# USB-to-Quad-RS-485-Conv-Module.net
KiCad netlist of a schematic drawn in EAGLE
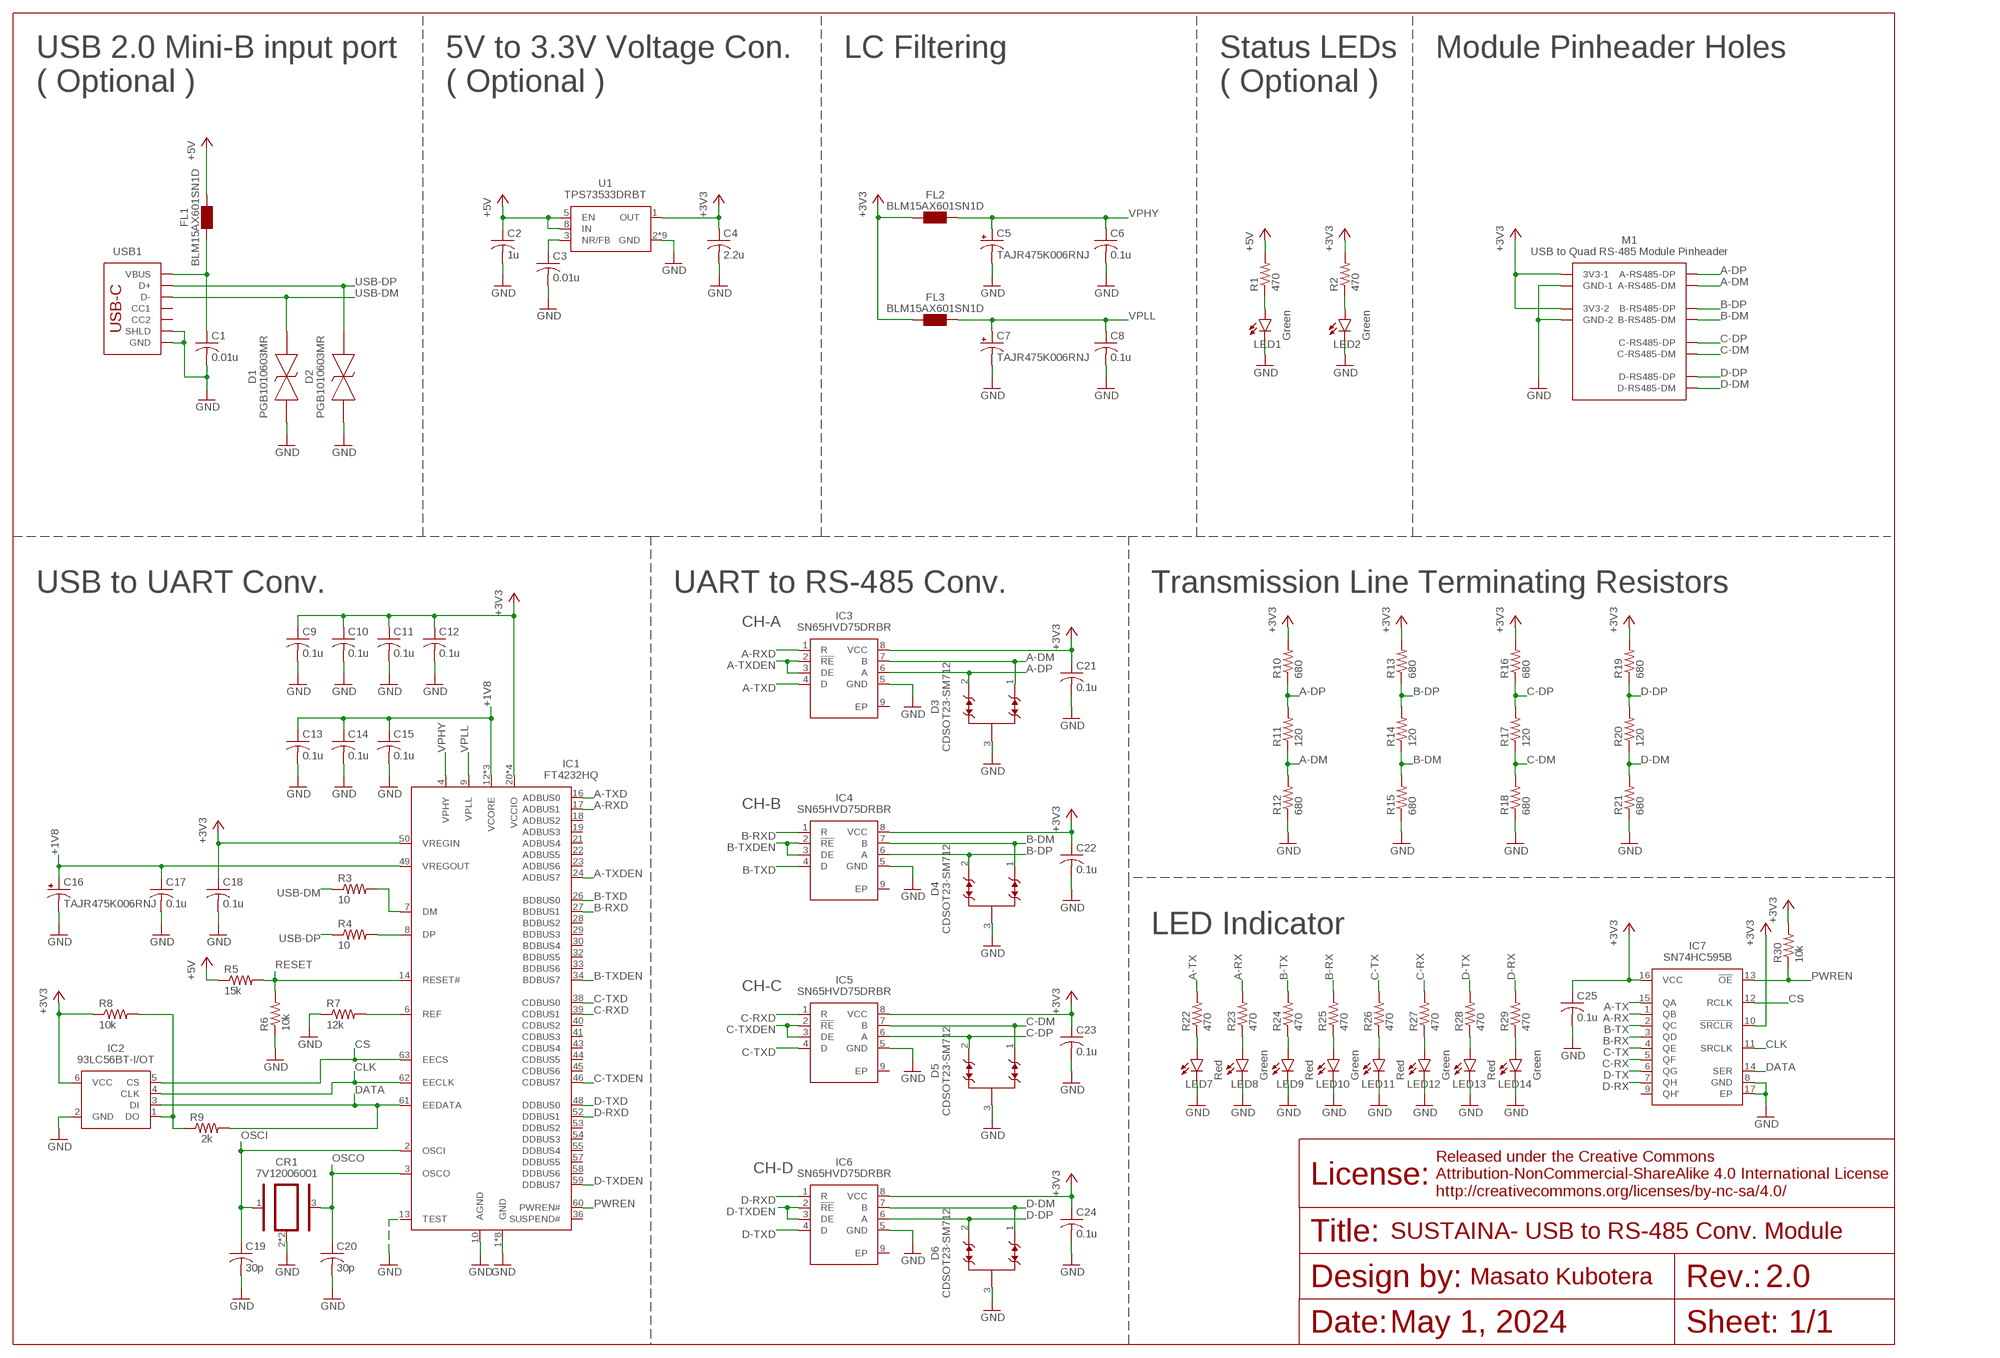
[diagram p0: schematic, sheet 1]

(export (version "E")
  (design (tool "Eeschema 10.0.6"))
  (components
    (comp (ref "C1")
      (value "0.01u")
      (footprint "eagle-import:C0402")
      (libsource (lib "eagle-import") (part "C-USC0402"))
    )
    (comp (ref "C2")
      (value "1u")
      (footprint "eagle-import:C0402")
      (libsource (lib "eagle-import") (part "C-USC0402"))
    )
    (comp (ref "C3")
      (value "0.01u")
      (footprint "eagle-import:C0402")
      (libsource (lib "eagle-import") (part "C-USC0402"))
    )
    (comp (ref "C4")
      (value "2.2u")
      (footprint "eagle-import:C0402")
      (libsource (lib "eagle-import") (part "C-USC0402"))
    )
    (comp (ref "C5")
      (value "4.7u")
      (footprint "eagle-import:0805K")
      (libsource (lib "eagle-import") (part "TAJR475K006RNJ"))
    )
    (comp (ref "C6")
      (value "0.1u")
      (footprint "eagle-import:C0402")
      (libsource (lib "eagle-import") (part "C-USC0402"))
    )
    (comp (ref "C7")
      (value "4.7u")
      (footprint "eagle-import:0805K")
      (libsource (lib "eagle-import") (part "TAJR475K006RNJ"))
    )
    (comp (ref "C8")
      (value "0.1u")
      (footprint "eagle-import:C0402")
      (libsource (lib "eagle-import") (part "C-USC0402"))
    )
    (comp (ref "C9")
      (value "0.1u")
      (footprint "eagle-import:C0402")
      (libsource (lib "eagle-import") (part "C-USC0402"))
    )
    (comp (ref "C10")
      (value "0.1u")
      (footprint "eagle-import:C0402")
      (libsource (lib "eagle-import") (part "C-USC0402"))
    )
    (comp (ref "C11")
      (value "0.1u")
      (footprint "eagle-import:C0402")
      (libsource (lib "eagle-import") (part "C-USC0402"))
    )
    (comp (ref "C12")
      (value "0.1u")
      (footprint "eagle-import:C0402")
      (libsource (lib "eagle-import") (part "C-USC0402"))
    )
    (comp (ref "C13")
      (value "0.1u")
      (footprint "eagle-import:C0402")
      (libsource (lib "eagle-import") (part "C-USC0402"))
    )
    (comp (ref "C14")
      (value "0.1u")
      (footprint "eagle-import:C0402")
      (libsource (lib "eagle-import") (part "C-USC0402"))
    )
    (comp (ref "C15")
      (value "0.1u")
      (footprint "eagle-import:C0402")
      (libsource (lib "eagle-import") (part "C-USC0402"))
    )
    (comp (ref "C16")
      (value "4.7u")
      (footprint "eagle-import:0805K")
      (libsource (lib "eagle-import") (part "TAJR475K006RNJ"))
    )
    (comp (ref "C17")
      (value "0.1u")
      (footprint "eagle-import:C0402")
      (libsource (lib "eagle-import") (part "C-USC0402"))
    )
    (comp (ref "C18")
      (value "0.1u")
      (footprint "eagle-import:C0402")
      (libsource (lib "eagle-import") (part "C-USC0402"))
    )
    (comp (ref "C19")
      (value "30p")
      (footprint "eagle-import:C0402")
      (libsource (lib "eagle-import") (part "C-USC0402"))
    )
    (comp (ref "C20")
      (value "30p")
      (footprint "eagle-import:C0402")
      (libsource (lib "eagle-import") (part "C-USC0402"))
    )
    (comp (ref "C21")
      (value "0.1u")
      (footprint "eagle-import:C0402")
      (libsource (lib "eagle-import") (part "C-USC0402"))
    )
    (comp (ref "C22")
      (value "0.1u")
      (footprint "eagle-import:C0402")
      (libsource (lib "eagle-import") (part "C-USC0402"))
    )
    (comp (ref "C23")
      (value "0.1u")
      (footprint "eagle-import:C0402")
      (libsource (lib "eagle-import") (part "C-USC0402"))
    )
    (comp (ref "C24")
      (value "0.1u")
      (footprint "eagle-import:C0402")
      (libsource (lib "eagle-import") (part "C-USC0402"))
    )
    (comp (ref "C25")
      (value "0.1u")
      (footprint "eagle-import:C0402")
      (libsource (lib "eagle-import") (part "C-USC0402"))
    )
    (comp (ref "CR1")
      (value "7V12006001")
      (footprint "eagle-import:7V12006001")
      (libsource (lib "eagle-import") (part "7V12006001"))
    )
    (comp (ref "D1")
      (value "PGB1010603MR")
      (footprint "eagle-import:0603")
      (libsource (lib "eagle-import") (part "PGB1010603MR"))
    )
    (comp (ref "D2")
      (value "PGB1010603MR")
      (footprint "eagle-import:0603")
      (libsource (lib "eagle-import") (part "PGB1010603MR"))
    )
    (comp (ref "D3")
      (value "CDSOT23-SM712")
      (footprint "eagle-import:SOT-23-3")
      (libsource (lib "eagle-import") (part "CDSOT23-SM712"))
    )
    (comp (ref "D4")
      (value "CDSOT23-SM712")
      (footprint "eagle-import:SOT-23-3")
      (libsource (lib "eagle-import") (part "CDSOT23-SM712"))
    )
    (comp (ref "D5")
      (value "CDSOT23-SM712")
      (footprint "eagle-import:SOT-23-3")
      (libsource (lib "eagle-import") (part "CDSOT23-SM712"))
    )
    (comp (ref "D6")
      (value "CDSOT23-SM712")
      (footprint "eagle-import:SOT-23-3")
      (libsource (lib "eagle-import") (part "CDSOT23-SM712"))
    )
    (comp (ref "FL1")
      (value "BLM15AX601SN1D")
      (footprint "eagle-import:BLM15AX601SN1D")
      (libsource (lib "eagle-import") (part "BLM15AX601SN1D"))
    )
    (comp (ref "FL2")
      (value "BLM15AX601SN1D")
      (footprint "eagle-import:BLM15AX601SN1D")
      (libsource (lib "eagle-import") (part "BLM15AX601SN1D"))
    )
    (comp (ref "FL3")
      (value "BLM15AX601SN1D")
      (footprint "eagle-import:BLM15AX601SN1D")
      (libsource (lib "eagle-import") (part "BLM15AX601SN1D"))
    )
    (comp (ref "IC1")
      (value "FT4232HQ")
      (footprint "eagle-import:FT4232HQ")
      (libsource (lib "eagle-import") (part "FT4232HQ"))
    )
    (comp (ref "IC2")
      (value "93LC56BT-I/OT")
      (footprint "eagle-import:SOT-23-6")
      (libsource (lib "eagle-import") (part "93LC56BT-I/OT"))
    )
    (comp (ref "IC3")
      (value "SN65HVD75DRBR")
      (footprint "eagle-import:SON65P300X300X100-9N")
      (libsource (lib "eagle-import") (part "SN65HVD75DRBR"))
    )
    (comp (ref "IC4")
      (value "SN65HVD75DRBR")
      (footprint "eagle-import:SON65P300X300X100-9N")
      (libsource (lib "eagle-import") (part "SN65HVD75DRBR"))
    )
    (comp (ref "IC5")
      (value "SN65HVD75DRBR")
      (footprint "eagle-import:SON65P300X300X100-9N")
      (libsource (lib "eagle-import") (part "SN65HVD75DRBR"))
    )
    (comp (ref "IC6")
      (value "SN65HVD75DRBR")
      (footprint "eagle-import:SON65P300X300X100-9N")
      (libsource (lib "eagle-import") (part "SN65HVD75DRBR"))
    )
    (comp (ref "IC7")
      (value "SN74HC595B")
      (footprint "eagle-import:QFN40P250X250X50-17N")
      (libsource (lib "eagle-import") (part "SN74HC595B"))
    )
    (comp (ref "LED1")
      (value "Green")
      (footprint "eagle-import:SML0603")
      (libsource (lib "eagle-import") (part "LEDSML0603"))
    )
    (comp (ref "LED2")
      (value "Green")
      (footprint "eagle-import:SML0603")
      (libsource (lib "eagle-import") (part "LEDSML0603"))
    )
    (comp (ref "LED7")
      (value "Red")
      (footprint "eagle-import:SML0603")
      (libsource (lib "eagle-import") (part "LEDSML0603"))
    )
    (comp (ref "LED8")
      (value "Green")
      (footprint "eagle-import:SML0603")
      (libsource (lib "eagle-import") (part "LEDSML0603"))
    )
    (comp (ref "LED9")
      (value "Red")
      (footprint "eagle-import:SML0603")
      (libsource (lib "eagle-import") (part "LEDSML0603"))
    )
    (comp (ref "LED10")
      (value "Green")
      (footprint "eagle-import:SML0603")
      (libsource (lib "eagle-import") (part "LEDSML0603"))
    )
    (comp (ref "LED11")
      (value "Red")
      (footprint "eagle-import:SML0603")
      (libsource (lib "eagle-import") (part "LEDSML0603"))
    )
    (comp (ref "LED12")
      (value "Green")
      (footprint "eagle-import:SML0603")
      (libsource (lib "eagle-import") (part "LEDSML0603"))
    )
    (comp (ref "LED13")
      (value "Red")
      (footprint "eagle-import:SML0603")
      (libsource (lib "eagle-import") (part "LEDSML0603"))
    )
    (comp (ref "LED14")
      (value "Green")
      (footprint "eagle-import:SML0603")
      (libsource (lib "eagle-import") (part "LEDSML0603"))
    )
    (comp (ref "M1")
      (value "USB-TO-QUAD-RS-485-CONV-MODULEDIMENSION")
      (footprint "eagle-import:USB-TO-QUAD-RS-485-CONV-MODULE-DIMENSION")
      (libsource (lib "eagle-import") (part "USB-TO-QUAD-RS-485-CONV-MODULEDIMENSION"))
    )
    (comp (ref "R1")
      (value "470")
      (footprint "eagle-import:R0402")
      (libsource (lib "eagle-import") (part "R-US_R0402"))
    )
    (comp (ref "R2")
      (value "470")
      (footprint "eagle-import:R0402")
      (libsource (lib "eagle-import") (part "R-US_R0402"))
    )
    (comp (ref "R3")
      (value "10")
      (footprint "eagle-import:R0402")
      (libsource (lib "eagle-import") (part "R-US_R0402"))
    )
    (comp (ref "R4")
      (value "10")
      (footprint "eagle-import:R0402")
      (libsource (lib "eagle-import") (part "R-US_R0402"))
    )
    (comp (ref "R5")
      (value "15k")
      (footprint "eagle-import:R0402")
      (libsource (lib "eagle-import") (part "R-US_R0402"))
    )
    (comp (ref "R6")
      (value "10k")
      (footprint "eagle-import:R0402")
      (libsource (lib "eagle-import") (part "R-US_R0402"))
    )
    (comp (ref "R7")
      (value "12k")
      (footprint "eagle-import:R0402")
      (libsource (lib "eagle-import") (part "R-US_R0402"))
    )
    (comp (ref "R8")
      (value "10k")
      (footprint "eagle-import:R0402")
      (libsource (lib "eagle-import") (part "R-US_R0402"))
    )
    (comp (ref "R9")
      (value "2k")
      (footprint "eagle-import:R0402")
      (libsource (lib "eagle-import") (part "R-US_R0402"))
    )
    (comp (ref "R10")
      (value "680")
      (footprint "eagle-import:R0402")
      (libsource (lib "eagle-import") (part "R-US_R0402"))
    )
    (comp (ref "R11")
      (value "120")
      (footprint "eagle-import:R0402")
      (libsource (lib "eagle-import") (part "R-US_R0402"))
    )
    (comp (ref "R12")
      (value "680")
      (footprint "eagle-import:R0402")
      (libsource (lib "eagle-import") (part "R-US_R0402"))
    )
    (comp (ref "R13")
      (value "680")
      (footprint "eagle-import:R0402")
      (libsource (lib "eagle-import") (part "R-US_R0402"))
    )
    (comp (ref "R14")
      (value "120")
      (footprint "eagle-import:R0402")
      (libsource (lib "eagle-import") (part "R-US_R0402"))
    )
    (comp (ref "R15")
      (value "680")
      (footprint "eagle-import:R0402")
      (libsource (lib "eagle-import") (part "R-US_R0402"))
    )
    (comp (ref "R16")
      (value "680")
      (footprint "eagle-import:R0402")
      (libsource (lib "eagle-import") (part "R-US_R0402"))
    )
    (comp (ref "R17")
      (value "120")
      (footprint "eagle-import:R0402")
      (libsource (lib "eagle-import") (part "R-US_R0402"))
    )
    (comp (ref "R18")
      (value "680")
      (footprint "eagle-import:R0402")
      (libsource (lib "eagle-import") (part "R-US_R0402"))
    )
    (comp (ref "R19")
      (value "680")
      (footprint "eagle-import:R0402")
      (libsource (lib "eagle-import") (part "R-US_R0402"))
    )
    (comp (ref "R20")
      (value "120")
      (footprint "eagle-import:R0402")
      (libsource (lib "eagle-import") (part "R-US_R0402"))
    )
    (comp (ref "R21")
      (value "680")
      (footprint "eagle-import:R0402")
      (libsource (lib "eagle-import") (part "R-US_R0402"))
    )
    (comp (ref "R22")
      (value "470")
      (footprint "eagle-import:R0402")
      (libsource (lib "eagle-import") (part "R-US_R0402"))
    )
    (comp (ref "R23")
      (value "470")
      (footprint "eagle-import:R0402")
      (libsource (lib "eagle-import") (part "R-US_R0402"))
    )
    (comp (ref "R24")
      (value "470")
      (footprint "eagle-import:R0402")
      (libsource (lib "eagle-import") (part "R-US_R0402"))
    )
    (comp (ref "R25")
      (value "470")
      (footprint "eagle-import:R0402")
      (libsource (lib "eagle-import") (part "R-US_R0402"))
    )
    (comp (ref "R26")
      (value "470")
      (footprint "eagle-import:R0402")
      (libsource (lib "eagle-import") (part "R-US_R0402"))
    )
    (comp (ref "R27")
      (value "470")
      (footprint "eagle-import:R0402")
      (libsource (lib "eagle-import") (part "R-US_R0402"))
    )
    (comp (ref "R28")
      (value "470")
      (footprint "eagle-import:R0402")
      (libsource (lib "eagle-import") (part "R-US_R0402"))
    )
    (comp (ref "R29")
      (value "470")
      (footprint "eagle-import:R0402")
      (libsource (lib "eagle-import") (part "R-US_R0402"))
    )
    (comp (ref "R30")
      (value "10k")
      (footprint "eagle-import:R0402")
      (libsource (lib "eagle-import") (part "R-US_R0402"))
    )
    (comp (ref "U1")
      (value "TPS73533DRBT")
      (footprint "eagle-import:SON-8")
      (libsource (lib "eagle-import") (part "TPS73533DRBT"))
    )
    (comp (ref "USB1")
      (value "USB-C-2.0")
      (footprint "eagle-import:USB-C-2.0")
      (libsource (lib "eagle-import") (part "USB-C-2.0"))
    )
  )
  (nets
    (net (code "1") (name "+3V3") (class "Default")
      (node (ref "C10") (pin "1") (pinfunction "1_1") (pintype "passive"))
      (node (ref "C11") (pin "1") (pinfunction "1_1") (pintype "passive"))
      (node (ref "C12") (pin "1") (pinfunction "1_1") (pintype "passive"))
      (node (ref "C18") (pin "1") (pinfunction "1_1") (pintype "passive"))
      (node (ref "C21") (pin "1") (pinfunction "1_1") (pintype "passive"))
      (node (ref "C22") (pin "1") (pinfunction "1_1") (pintype "passive"))
      (node (ref "C23") (pin "1") (pinfunction "1_1") (pintype "passive"))
      (node (ref "C24") (pin "1") (pinfunction "1_1") (pintype "passive"))
      (node (ref "C25") (pin "1") (pinfunction "1_1") (pintype "passive"))
      (node (ref "C4") (pin "1") (pinfunction "1_1") (pintype "passive"))
      (node (ref "C9") (pin "1") (pinfunction "1_1") (pintype "passive"))
      (node (ref "FL2") (pin "1") (pinfunction "1_1") (pintype "bidirectional"))
      (node (ref "FL3") (pin "1") (pinfunction "1_1") (pintype "bidirectional"))
      (node (ref "IC1") (pin "20") (pinfunction "VCCIO_20") (pintype "bidirectional"))
      (node (ref "IC1") (pin "31") (pinfunction "VCCIO_31") (pintype "bidirectional"))
      (node (ref "IC1") (pin "42") (pinfunction "VCCIO_42") (pintype "bidirectional"))
      (node (ref "IC1") (pin "50") (pinfunction "VREGIN_50") (pintype "bidirectional"))
      (node (ref "IC1") (pin "56") (pinfunction "VCCIO_56") (pintype "bidirectional"))
      (node (ref "IC2") (pin "6") (pinfunction "VCC_6") (pintype "bidirectional"))
      (node (ref "IC3") (pin "8") (pinfunction "VCC_8") (pintype "bidirectional"))
      (node (ref "IC4") (pin "8") (pinfunction "VCC_8") (pintype "bidirectional"))
      (node (ref "IC5") (pin "8") (pinfunction "VCC_8") (pintype "bidirectional"))
      (node (ref "IC6") (pin "8") (pinfunction "VCC_8") (pintype "bidirectional"))
      (node (ref "IC7") (pin "10") (pinfunction "~{SRCLR}_10") (pintype "bidirectional"))
      (node (ref "IC7") (pin "16") (pinfunction "VCC_16") (pintype "bidirectional"))
      (node (ref "M1") (pin "3V3-1") (pinfunction "3V3-1_3V3-1") (pintype "bidirectional"))
      (node (ref "M1") (pin "3V3-2") (pinfunction "3V3-2_3V3-2") (pintype "bidirectional"))
      (node (ref "R10") (pin "2") (pinfunction "2_2") (pintype "passive"))
      (node (ref "R13") (pin "2") (pinfunction "2_2") (pintype "passive"))
      (node (ref "R16") (pin "2") (pinfunction "2_2") (pintype "passive"))
      (node (ref "R19") (pin "2") (pinfunction "2_2") (pintype "passive"))
      (node (ref "R2") (pin "2") (pinfunction "2_2") (pintype "passive"))
      (node (ref "R30") (pin "2") (pinfunction "2_2") (pintype "passive"))
      (node (ref "R8") (pin "1") (pinfunction "1_1") (pintype "passive"))
      (node (ref "U1") (pin "1") (pinfunction "OUT_1") (pintype "output"))
    )
    (net (code "2") (name "+5V") (class "Default")
      (node (ref "C2") (pin "1") (pinfunction "1_1") (pintype "passive"))
      (node (ref "FL1") (pin "2") (pinfunction "2_2") (pintype "bidirectional"))
      (node (ref "R1") (pin "2") (pinfunction "2_2") (pintype "passive"))
      (node (ref "R5") (pin "1") (pinfunction "1_1") (pintype "passive"))
      (node (ref "U1") (pin "5") (pinfunction "EN_5") (pintype "input"))
      (node (ref "U1") (pin "8") (pinfunction "IN_8") (pintype "input"))
    )
    (net (code "3") (name "/+1V8") (class "Default")
      (node (ref "C13") (pin "1") (pinfunction "1_1") (pintype "passive"))
      (node (ref "C14") (pin "1") (pinfunction "1_1") (pintype "passive"))
      (node (ref "C15") (pin "1") (pinfunction "1_1") (pintype "passive"))
      (node (ref "C16") (pin "1") (pinfunction "+_1") (pintype "passive"))
      (node (ref "C17") (pin "1") (pinfunction "1_1") (pintype "passive"))
      (node (ref "IC1") (pin "12") (pinfunction "VCORE_12") (pintype "bidirectional"))
      (node (ref "IC1") (pin "37") (pinfunction "VCORE_37") (pintype "bidirectional"))
      (node (ref "IC1") (pin "49") (pinfunction "VREGOUT_49") (pintype "bidirectional"))
      (node (ref "IC1") (pin "64") (pinfunction "VCORE_64") (pintype "bidirectional"))
    )
    (net (code "4") (name "/A-DM") (class "Default")
      (node (ref "D3") (pin "1") (pinfunction "1_1") (pintype "bidirectional"))
      (node (ref "IC3") (pin "7") (pinfunction "B_7") (pintype "bidirectional"))
      (node (ref "M1") (pin "A-RS-485-DM") (pinfunction "A-RS485-DM_A-RS-485-DM") (pintype "bidirectional"))
      (node (ref "R11") (pin "1") (pinfunction "1_1") (pintype "passive"))
      (node (ref "R12") (pin "2") (pinfunction "2_2") (pintype "passive"))
    )
    (net (code "5") (name "/A-DP") (class "Default")
      (node (ref "D3") (pin "2") (pinfunction "2_2") (pintype "bidirectional"))
      (node (ref "IC3") (pin "6") (pinfunction "A_6") (pintype "bidirectional"))
      (node (ref "M1") (pin "A-RS-485-DP") (pinfunction "A-RS485-DP_A-RS-485-DP") (pintype "bidirectional"))
      (node (ref "R10") (pin "1") (pinfunction "1_1") (pintype "passive"))
      (node (ref "R11") (pin "2") (pinfunction "2_2") (pintype "passive"))
    )
    (net (code "6") (name "/A-RX") (class "Default")
      (node (ref "IC7") (pin "1") (pinfunction "QB_1") (pintype "bidirectional"))
      (node (ref "R23") (pin "2") (pinfunction "2_2") (pintype "passive"))
    )
    (net (code "7") (name "/A-RXD") (class "Default")
      (node (ref "IC1") (pin "17") (pinfunction "ADBUS1_17") (pintype "bidirectional"))
      (node (ref "IC3") (pin "1") (pinfunction "R_1") (pintype "bidirectional"))
    )
    (net (code "8") (name "/A-TX") (class "Default")
      (node (ref "IC7") (pin "15") (pinfunction "QA_15") (pintype "bidirectional"))
      (node (ref "R22") (pin "2") (pinfunction "2_2") (pintype "passive"))
    )
    (net (code "9") (name "/A-TXD") (class "Default")
      (node (ref "IC1") (pin "16") (pinfunction "ADBUS0_16") (pintype "bidirectional"))
      (node (ref "IC3") (pin "4") (pinfunction "D_4") (pintype "bidirectional"))
    )
    (net (code "10") (name "/A-TXDEN") (class "Default")
      (node (ref "IC1") (pin "24") (pinfunction "ADBUS7_24") (pintype "bidirectional"))
      (node (ref "IC3") (pin "2") (pinfunction "~{RE}_2") (pintype "bidirectional"))
      (node (ref "IC3") (pin "3") (pinfunction "DE_3") (pintype "bidirectional"))
    )
    (net (code "11") (name "/B-DM") (class "Default")
      (node (ref "D4") (pin "1") (pinfunction "1_1") (pintype "bidirectional"))
      (node (ref "IC4") (pin "7") (pinfunction "B_7") (pintype "bidirectional"))
      (node (ref "M1") (pin "B-RS-485-DM") (pinfunction "B-RS485-DM_B-RS-485-DM") (pintype "bidirectional"))
      (node (ref "R14") (pin "1") (pinfunction "1_1") (pintype "passive"))
      (node (ref "R15") (pin "2") (pinfunction "2_2") (pintype "passive"))
    )
    (net (code "12") (name "/B-DP") (class "Default")
      (node (ref "D4") (pin "2") (pinfunction "2_2") (pintype "bidirectional"))
      (node (ref "IC4") (pin "6") (pinfunction "A_6") (pintype "bidirectional"))
      (node (ref "M1") (pin "B-RS-485-DP") (pinfunction "B-RS485-DP_B-RS-485-DP") (pintype "bidirectional"))
      (node (ref "R13") (pin "1") (pinfunction "1_1") (pintype "passive"))
      (node (ref "R14") (pin "2") (pinfunction "2_2") (pintype "passive"))
    )
    (net (code "13") (name "/B-RX") (class "Default")
      (node (ref "IC7") (pin "3") (pinfunction "QD_3") (pintype "bidirectional"))
      (node (ref "R25") (pin "2") (pinfunction "2_2") (pintype "passive"))
    )
    (net (code "14") (name "/B-RXD") (class "Default")
      (node (ref "IC1") (pin "27") (pinfunction "BDBUS1_27") (pintype "bidirectional"))
      (node (ref "IC4") (pin "1") (pinfunction "R_1") (pintype "bidirectional"))
    )
    (net (code "15") (name "/B-TX") (class "Default")
      (node (ref "IC7") (pin "2") (pinfunction "QC_2") (pintype "bidirectional"))
      (node (ref "R24") (pin "2") (pinfunction "2_2") (pintype "passive"))
    )
    (net (code "16") (name "/B-TXD") (class "Default")
      (node (ref "IC1") (pin "26") (pinfunction "BDBUS0_26") (pintype "bidirectional"))
      (node (ref "IC4") (pin "4") (pinfunction "D_4") (pintype "bidirectional"))
    )
    (net (code "17") (name "/B-TXDEN") (class "Default")
      (node (ref "IC1") (pin "34") (pinfunction "BDBUS7_34") (pintype "bidirectional"))
      (node (ref "IC4") (pin "2") (pinfunction "~{RE}_2") (pintype "bidirectional"))
      (node (ref "IC4") (pin "3") (pinfunction "DE_3") (pintype "bidirectional"))
    )
    (net (code "18") (name "/C-DM") (class "Default")
      (node (ref "D5") (pin "1") (pinfunction "1_1") (pintype "bidirectional"))
      (node (ref "IC5") (pin "7") (pinfunction "B_7") (pintype "bidirectional"))
      (node (ref "M1") (pin "C-RS-485-DM") (pinfunction "C-RS485-DM_C-RS-485-DM") (pintype "bidirectional"))
      (node (ref "R17") (pin "1") (pinfunction "1_1") (pintype "passive"))
      (node (ref "R18") (pin "2") (pinfunction "2_2") (pintype "passive"))
    )
    (net (code "19") (name "/C-DP") (class "Default")
      (node (ref "D5") (pin "2") (pinfunction "2_2") (pintype "bidirectional"))
      (node (ref "IC5") (pin "6") (pinfunction "A_6") (pintype "bidirectional"))
      (node (ref "M1") (pin "C-RS-485-DP") (pinfunction "C-RS485-DP_C-RS-485-DP") (pintype "bidirectional"))
      (node (ref "R16") (pin "1") (pinfunction "1_1") (pintype "passive"))
      (node (ref "R17") (pin "2") (pinfunction "2_2") (pintype "passive"))
    )
    (net (code "20") (name "/C-RX") (class "Default")
      (node (ref "IC7") (pin "5") (pinfunction "QF_5") (pintype "bidirectional"))
      (node (ref "R27") (pin "2") (pinfunction "2_2") (pintype "passive"))
    )
    (net (code "21") (name "/C-RXD") (class "Default")
      (node (ref "IC1") (pin "39") (pinfunction "CDBUS1_39") (pintype "bidirectional"))
      (node (ref "IC5") (pin "1") (pinfunction "R_1") (pintype "bidirectional"))
    )
    (net (code "22") (name "/C-TX") (class "Default")
      (node (ref "IC7") (pin "4") (pinfunction "QE_4") (pintype "bidirectional"))
      (node (ref "R26") (pin "2") (pinfunction "2_2") (pintype "passive"))
    )
    (net (code "23") (name "/C-TXD") (class "Default")
      (node (ref "IC1") (pin "38") (pinfunction "CDBUS0_38") (pintype "bidirectional"))
      (node (ref "IC5") (pin "4") (pinfunction "D_4") (pintype "bidirectional"))
    )
    (net (code "24") (name "/C-TXDEN") (class "Default")
      (node (ref "IC1") (pin "46") (pinfunction "CDBUS7_46") (pintype "bidirectional"))
      (node (ref "IC5") (pin "2") (pinfunction "~{RE}_2") (pintype "bidirectional"))
      (node (ref "IC5") (pin "3") (pinfunction "DE_3") (pintype "bidirectional"))
    )
    (net (code "25") (name "/CLK") (class "Default")
      (node (ref "IC1") (pin "62") (pinfunction "EECLK_62") (pintype "bidirectional"))
      (node (ref "IC2") (pin "4") (pinfunction "CLK_4") (pintype "bidirectional"))
      (node (ref "IC7") (pin "11") (pinfunction "SRCLK_11") (pintype "bidirectional"))
    )
    (net (code "26") (name "/CS") (class "Default")
      (node (ref "IC1") (pin "63") (pinfunction "EECS_63") (pintype "bidirectional"))
      (node (ref "IC2") (pin "5") (pinfunction "CS_5") (pintype "bidirectional"))
      (node (ref "IC7") (pin "12") (pinfunction "RCLK_12") (pintype "bidirectional"))
    )
    (net (code "27") (name "/D-DM") (class "Default")
      (node (ref "D6") (pin "1") (pinfunction "1_1") (pintype "bidirectional"))
      (node (ref "IC6") (pin "7") (pinfunction "B_7") (pintype "bidirectional"))
      (node (ref "M1") (pin "D-RS-485-DM") (pinfunction "D-RS485-DM_D-RS-485-DM") (pintype "bidirectional"))
      (node (ref "R20") (pin "1") (pinfunction "1_1") (pintype "passive"))
      (node (ref "R21") (pin "2") (pinfunction "2_2") (pintype "passive"))
    )
    (net (code "28") (name "/D-DP") (class "Default")
      (node (ref "D6") (pin "2") (pinfunction "2_2") (pintype "bidirectional"))
      (node (ref "IC6") (pin "6") (pinfunction "A_6") (pintype "bidirectional"))
      (node (ref "M1") (pin "D-RS-485-DP") (pinfunction "D-RS485-DP_D-RS-485-DP") (pintype "bidirectional"))
      (node (ref "R19") (pin "1") (pinfunction "1_1") (pintype "passive"))
      (node (ref "R20") (pin "2") (pinfunction "2_2") (pintype "passive"))
    )
    (net (code "29") (name "/D-RX") (class "Default")
      (node (ref "IC7") (pin "7") (pinfunction "QH_7") (pintype "bidirectional"))
      (node (ref "R29") (pin "2") (pinfunction "2_2") (pintype "passive"))
    )
    (net (code "30") (name "/D-RXD") (class "Default")
      (node (ref "IC1") (pin "52") (pinfunction "DDBUS1_52") (pintype "bidirectional"))
      (node (ref "IC6") (pin "1") (pinfunction "R_1") (pintype "bidirectional"))
    )
    (net (code "31") (name "/D-TX") (class "Default")
      (node (ref "IC7") (pin "6") (pinfunction "QG_6") (pintype "bidirectional"))
      (node (ref "R28") (pin "2") (pinfunction "2_2") (pintype "passive"))
    )
    (net (code "32") (name "/D-TXD") (class "Default")
      (node (ref "IC1") (pin "48") (pinfunction "DDBUS0_48") (pintype "bidirectional"))
      (node (ref "IC6") (pin "4") (pinfunction "D_4") (pintype "bidirectional"))
    )
    (net (code "33") (name "/D-TXDEN") (class "Default")
      (node (ref "IC1") (pin "59") (pinfunction "DDBUS7_59") (pintype "bidirectional"))
      (node (ref "IC6") (pin "2") (pinfunction "~{RE}_2") (pintype "bidirectional"))
      (node (ref "IC6") (pin "3") (pinfunction "DE_3") (pintype "bidirectional"))
    )
    (net (code "34") (name "/DATA") (class "Default")
      (node (ref "IC1") (pin "61") (pinfunction "EEDATA_61") (pintype "bidirectional"))
      (node (ref "IC2") (pin "3") (pinfunction "DI_3") (pintype "bidirectional"))
      (node (ref "IC7") (pin "14") (pinfunction "SER_14") (pintype "bidirectional"))
      (node (ref "R9") (pin "2") (pinfunction "2_2") (pintype "passive"))
    )
    (net (code "35") (name "/OSCI") (class "Default")
      (node (ref "C19") (pin "1") (pinfunction "1_1") (pintype "passive"))
      (node (ref "CR1") (pin "1") (pinfunction "P$1_1") (pintype "bidirectional"))
      (node (ref "IC1") (pin "2") (pinfunction "OSCI_2") (pintype "bidirectional"))
    )
    (net (code "36") (name "/OSCO") (class "Default")
      (node (ref "C20") (pin "1") (pinfunction "1_1") (pintype "passive"))
      (node (ref "CR1") (pin "3") (pinfunction "P$2_3") (pintype "bidirectional"))
      (node (ref "IC1") (pin "3") (pinfunction "OSCO_3") (pintype "bidirectional"))
    )
    (net (code "37") (name "/PWREN") (class "Default")
      (node (ref "IC1") (pin "60") (pinfunction "PWREN#_60") (pintype "bidirectional"))
      (node (ref "IC7") (pin "13") (pinfunction "~{OE}_13") (pintype "bidirectional"))
      (node (ref "R30") (pin "1") (pinfunction "1_1") (pintype "passive"))
    )
    (net (code "38") (name "/RESET") (class "Default")
      (node (ref "IC1") (pin "14") (pinfunction "RESET#_14") (pintype "bidirectional"))
      (node (ref "R5") (pin "2") (pinfunction "2_2") (pintype "passive"))
      (node (ref "R6") (pin "2") (pinfunction "2_2") (pintype "passive"))
    )
    (net (code "39") (name "/USB-DM") (class "Default")
      (node (ref "D1") (pin "2") (pinfunction "2_2") (pintype "bidirectional"))
      (node (ref "R3") (pin "1") (pinfunction "1_1") (pintype "passive"))
      (node (ref "USB1") (pin "A7") (pinfunction "D-_A7") (pintype "bidirectional"))
      (node (ref "USB1") (pin "B7") (pinfunction "D-_B7") (pintype "bidirectional"))
    )
    (net (code "40") (name "/USB-DP") (class "Default")
      (node (ref "D2") (pin "2") (pinfunction "2_2") (pintype "bidirectional"))
      (node (ref "R4") (pin "1") (pinfunction "1_1") (pintype "passive"))
      (node (ref "USB1") (pin "A6") (pinfunction "D+_A6") (pintype "bidirectional"))
      (node (ref "USB1") (pin "B6") (pinfunction "D+_B6") (pintype "bidirectional"))
    )
    (net (code "41") (name "/VPHY") (class "Default")
      (node (ref "C5") (pin "1") (pinfunction "+_1") (pintype "passive"))
      (node (ref "C6") (pin "1") (pinfunction "1_1") (pintype "passive"))
      (node (ref "FL2") (pin "2") (pinfunction "2_2") (pintype "bidirectional"))
      (node (ref "IC1") (pin "4") (pinfunction "VPHY_4") (pintype "bidirectional"))
    )
    (net (code "42") (name "/VPLL") (class "Default")
      (node (ref "C7") (pin "1") (pinfunction "+_1") (pintype "passive"))
      (node (ref "C8") (pin "1") (pinfunction "1_1") (pintype "passive"))
      (node (ref "FL3") (pin "2") (pinfunction "2_2") (pintype "bidirectional"))
      (node (ref "IC1") (pin "9") (pinfunction "VPLL_9") (pintype "bidirectional"))
    )
    (net (code "43") (name "GND") (class "Default")
      (node (ref "C1") (pin "2") (pinfunction "2_2") (pintype "passive"))
      (node (ref "C10") (pin "2") (pinfunction "2_2") (pintype "passive"))
      (node (ref "C11") (pin "2") (pinfunction "2_2") (pintype "passive"))
      (node (ref "C12") (pin "2") (pinfunction "2_2") (pintype "passive"))
      (node (ref "C13") (pin "2") (pinfunction "2_2") (pintype "passive"))
      (node (ref "C14") (pin "2") (pinfunction "2_2") (pintype "passive"))
      (node (ref "C15") (pin "2") (pinfunction "2_2") (pintype "passive"))
      (node (ref "C16") (pin "2") (pinfunction "-_2") (pintype "passive"))
      (node (ref "C17") (pin "2") (pinfunction "2_2") (pintype "passive"))
      (node (ref "C18") (pin "2") (pinfunction "2_2") (pintype "passive"))
      (node (ref "C19") (pin "2") (pinfunction "2_2") (pintype "passive"))
      (node (ref "C2") (pin "2") (pinfunction "2_2") (pintype "passive"))
      (node (ref "C20") (pin "2") (pinfunction "2_2") (pintype "passive"))
      (node (ref "C21") (pin "2") (pinfunction "2_2") (pintype "passive"))
      (node (ref "C22") (pin "2") (pinfunction "2_2") (pintype "passive"))
      (node (ref "C23") (pin "2") (pinfunction "2_2") (pintype "passive"))
      (node (ref "C24") (pin "2") (pinfunction "2_2") (pintype "passive"))
      (node (ref "C25") (pin "2") (pinfunction "2_2") (pintype "passive"))
      (node (ref "C3") (pin "2") (pinfunction "2_2") (pintype "passive"))
      (node (ref "C4") (pin "2") (pinfunction "2_2") (pintype "passive"))
      (node (ref "C5") (pin "2") (pinfunction "-_2") (pintype "passive"))
      (node (ref "C6") (pin "2") (pinfunction "2_2") (pintype "passive"))
      (node (ref "C7") (pin "2") (pinfunction "-_2") (pintype "passive"))
      (node (ref "C8") (pin "2") (pinfunction "2_2") (pintype "passive"))
      (node (ref "C9") (pin "2") (pinfunction "2_2") (pintype "passive"))
      (node (ref "CR1") (pin "2") (pinfunction "P$3_2") (pintype "bidirectional"))
      (node (ref "CR1") (pin "4") (pinfunction "P$3_4") (pintype "bidirectional"))
      (node (ref "D1") (pin "1") (pinfunction "1_1") (pintype "bidirectional"))
      (node (ref "D2") (pin "1") (pinfunction "1_1") (pintype "bidirectional"))
      (node (ref "D3") (pin "3") (pinfunction "3_3") (pintype "bidirectional"))
      (node (ref "D4") (pin "3") (pinfunction "3_3") (pintype "bidirectional"))
      (node (ref "D5") (pin "3") (pinfunction "3_3") (pintype "bidirectional"))
      (node (ref "D6") (pin "3") (pinfunction "3_3") (pintype "bidirectional"))
      (node (ref "IC1") (pin "1") (pinfunction "GND_1") (pintype "bidirectional"))
      (node (ref "IC1") (pin "10") (pinfunction "AGND_10") (pintype "bidirectional"))
      (node (ref "IC1") (pin "11") (pinfunction "GND_11") (pintype "bidirectional"))
      (node (ref "IC1") (pin "13") (pinfunction "TEST_13") (pintype "bidirectional"))
      (node (ref "IC1") (pin "15") (pinfunction "GND_15") (pintype "bidirectional"))
      (node (ref "IC1") (pin "25") (pinfunction "GND_25") (pintype "bidirectional"))
      (node (ref "IC1") (pin "35") (pinfunction "GND_35") (pintype "bidirectional"))
      (node (ref "IC1") (pin "47") (pinfunction "GND_47") (pintype "bidirectional"))
      (node (ref "IC1") (pin "5") (pinfunction "GND_5") (pintype "bidirectional"))
      (node (ref "IC1") (pin "51") (pinfunction "GND_51") (pintype "bidirectional"))
      (node (ref "IC2") (pin "2") (pinfunction "GND_2") (pintype "bidirectional"))
      (node (ref "IC3") (pin "5") (pinfunction "GND_5") (pintype "bidirectional"))
      (node (ref "IC4") (pin "5") (pinfunction "GND_5") (pintype "bidirectional"))
      (node (ref "IC5") (pin "5") (pinfunction "GND_5") (pintype "bidirectional"))
      (node (ref "IC6") (pin "5") (pinfunction "GND_5") (pintype "bidirectional"))
      (node (ref "IC7") (pin "17") (pinfunction "EP_17") (pintype "bidirectional"))
      (node (ref "IC7") (pin "8") (pinfunction "GND_8") (pintype "bidirectional"))
      (node (ref "LED1") (pin "C") (pinfunction "C_C") (pintype "passive"))
      (node (ref "LED10") (pin "C") (pinfunction "C_C") (pintype "passive"))
      (node (ref "LED11") (pin "C") (pinfunction "C_C") (pintype "passive"))
      (node (ref "LED12") (pin "C") (pinfunction "C_C") (pintype "passive"))
      (node (ref "LED13") (pin "C") (pinfunction "C_C") (pintype "passive"))
      (node (ref "LED14") (pin "C") (pinfunction "C_C") (pintype "passive"))
      (node (ref "LED2") (pin "C") (pinfunction "C_C") (pintype "passive"))
      (node (ref "LED7") (pin "C") (pinfunction "C_C") (pintype "passive"))
      (node (ref "LED8") (pin "C") (pinfunction "C_C") (pintype "passive"))
      (node (ref "LED9") (pin "C") (pinfunction "C_C") (pintype "passive"))
      (node (ref "M1") (pin "GND-1") (pinfunction "GND-1_GND-1") (pintype "bidirectional"))
      (node (ref "M1") (pin "GND-2") (pinfunction "GND-2_GND-2") (pintype "bidirectional"))
      (node (ref "R12") (pin "1") (pinfunction "1_1") (pintype "passive"))
      (node (ref "R15") (pin "1") (pinfunction "1_1") (pintype "passive"))
      (node (ref "R18") (pin "1") (pinfunction "1_1") (pintype "passive"))
      (node (ref "R21") (pin "1") (pinfunction "1_1") (pintype "passive"))
      (node (ref "R6") (pin "1") (pinfunction "1_1") (pintype "passive"))
      (node (ref "R7") (pin "1") (pinfunction "1_1") (pintype "passive"))
      (node (ref "U1") (pin "10") (pinfunction "GND_10") (pintype "power_in"))
      (node (ref "U1") (pin "11") (pinfunction "GND_11") (pintype "power_in"))
      (node (ref "U1") (pin "12") (pinfunction "GND_12") (pintype "power_in"))
      (node (ref "U1") (pin "13") (pinfunction "GND_13") (pintype "power_in"))
      (node (ref "U1") (pin "2") (pinfunction "GND_2") (pintype "power_in"))
      (node (ref "U1") (pin "4") (pinfunction "GND_4") (pintype "power_in"))
      (node (ref "U1") (pin "6") (pinfunction "GND_6") (pintype "power_in"))
      (node (ref "U1") (pin "7") (pinfunction "GND_7") (pintype "power_in"))
      (node (ref "U1") (pin "9") (pinfunction "GND_9") (pintype "power_in"))
      (node (ref "USB1") (pin "GND") (pinfunction "GND_GND") (pintype "bidirectional"))
      (node (ref "USB1") (pin "GND2") (pinfunction "GND_GND2") (pintype "bidirectional"))
      (node (ref "USB1") (pin "SHLD1") (pinfunction "SHLD_SHLD1") (pintype "bidirectional"))
      (node (ref "USB1") (pin "SHLD2") (pinfunction "SHLD_SHLD2") (pintype "bidirectional"))
      (node (ref "USB1") (pin "SHLD3") (pinfunction "SHLD_SHLD3") (pintype "bidirectional"))
      (node (ref "USB1") (pin "SHLD4") (pinfunction "SHLD_SHLD4") (pintype "bidirectional"))
      (node (ref "USB1") (pin "SHLD5") (pinfunction "SHLD_SHLD5") (pintype "bidirectional"))
      (node (ref "USB1") (pin "SHLD6") (pinfunction "SHLD_SHLD6") (pintype "bidirectional"))
      (node (ref "USB1") (pin "SHLD7") (pinfunction "SHLD_SHLD7") (pintype "bidirectional"))
      (node (ref "USB1") (pin "SHLD8") (pinfunction "SHLD_SHLD8") (pintype "bidirectional"))
    )
    (net (code "44") (name "Net-(C1-Pad1)") (class "Default")
      (node (ref "C1") (pin "1") (pinfunction "1_1") (pintype "passive"))
      (node (ref "FL1") (pin "1") (pinfunction "1_1") (pintype "bidirectional"))
      (node (ref "USB1") (pin "VBUS1") (pinfunction "VBUS_VBUS1") (pintype "bidirectional"))
      (node (ref "USB1") (pin "VBUS2") (pinfunction "VBUS_VBUS2") (pintype "bidirectional"))
    )
    (net (code "45") (name "Net-(IC1-DM)") (class "Default")
      (node (ref "IC1") (pin "7") (pinfunction "DM_7") (pintype "bidirectional"))
      (node (ref "R3") (pin "2") (pinfunction "2_2") (pintype "passive"))
    )
    (net (code "46") (name "Net-(IC1-DP)") (class "Default")
      (node (ref "IC1") (pin "8") (pinfunction "DP_8") (pintype "bidirectional"))
      (node (ref "R4") (pin "2") (pinfunction "2_2") (pintype "passive"))
    )
    (net (code "47") (name "Net-(IC1-REF)") (class "Default")
      (node (ref "IC1") (pin "6") (pinfunction "REF_6") (pintype "bidirectional"))
      (node (ref "R7") (pin "2") (pinfunction "2_2") (pintype "passive"))
    )
    (net (code "48") (name "Net-(IC2-DO)") (class "Default")
      (node (ref "IC2") (pin "1") (pinfunction "DO_1") (pintype "bidirectional"))
      (node (ref "R8") (pin "2") (pinfunction "2_2") (pintype "passive"))
      (node (ref "R9") (pin "1") (pinfunction "1_1") (pintype "passive"))
    )
    (net (code "49") (name "Net-(LED1-PadA)") (class "Default")
      (node (ref "LED1") (pin "A") (pinfunction "A_A") (pintype "passive"))
      (node (ref "R1") (pin "1") (pinfunction "1_1") (pintype "passive"))
    )
    (net (code "50") (name "Net-(LED2-PadA)") (class "Default")
      (node (ref "LED2") (pin "A") (pinfunction "A_A") (pintype "passive"))
      (node (ref "R2") (pin "1") (pinfunction "1_1") (pintype "passive"))
    )
    (net (code "51") (name "Net-(LED7-PadA)") (class "Default")
      (node (ref "LED7") (pin "A") (pinfunction "A_A") (pintype "passive"))
      (node (ref "R22") (pin "1") (pinfunction "1_1") (pintype "passive"))
    )
    (net (code "52") (name "Net-(LED8-PadA)") (class "Default")
      (node (ref "LED8") (pin "A") (pinfunction "A_A") (pintype "passive"))
      (node (ref "R23") (pin "1") (pinfunction "1_1") (pintype "passive"))
    )
    (net (code "53") (name "Net-(LED9-PadA)") (class "Default")
      (node (ref "LED9") (pin "A") (pinfunction "A_A") (pintype "passive"))
      (node (ref "R24") (pin "1") (pinfunction "1_1") (pintype "passive"))
    )
    (net (code "54") (name "Net-(LED10-PadA)") (class "Default")
      (node (ref "LED10") (pin "A") (pinfunction "A_A") (pintype "passive"))
      (node (ref "R25") (pin "1") (pinfunction "1_1") (pintype "passive"))
    )
    (net (code "55") (name "Net-(LED11-PadA)") (class "Default")
      (node (ref "LED11") (pin "A") (pinfunction "A_A") (pintype "passive"))
      (node (ref "R26") (pin "1") (pinfunction "1_1") (pintype "passive"))
    )
    (net (code "56") (name "Net-(LED12-PadA)") (class "Default")
      (node (ref "LED12") (pin "A") (pinfunction "A_A") (pintype "passive"))
      (node (ref "R27") (pin "1") (pinfunction "1_1") (pintype "passive"))
    )
    (net (code "57") (name "Net-(LED13-PadA)") (class "Default")
      (node (ref "LED13") (pin "A") (pinfunction "A_A") (pintype "passive"))
      (node (ref "R28") (pin "1") (pinfunction "1_1") (pintype "passive"))
    )
    (net (code "58") (name "Net-(LED14-PadA)") (class "Default")
      (node (ref "LED14") (pin "A") (pinfunction "A_A") (pintype "passive"))
      (node (ref "R29") (pin "1") (pinfunction "1_1") (pintype "passive"))
    )
    (net (code "59") (name "Net-(U1-NR{slash}FB)") (class "Default")
      (node (ref "C3") (pin "1") (pinfunction "1_1") (pintype "passive"))
      (node (ref "U1") (pin "3") (pinfunction "NR/FB_3") (pintype "input"))
    )
    (net (code "60") (name "unconnected-(IC1-ADBUS2-Pad18)") (class "Default")
      (node (ref "IC1") (pin "18") (pinfunction "ADBUS2_18") (pintype "bidirectional"))
    )
    (net (code "61") (name "unconnected-(IC1-ADBUS3-Pad19)") (class "Default")
      (node (ref "IC1") (pin "19") (pinfunction "ADBUS3_19") (pintype "bidirectional"))
    )
    (net (code "62") (name "unconnected-(IC1-ADBUS4-Pad21)") (class "Default")
      (node (ref "IC1") (pin "21") (pinfunction "ADBUS4_21") (pintype "bidirectional"))
    )
    (net (code "63") (name "unconnected-(IC1-ADBUS5-Pad22)") (class "Default")
      (node (ref "IC1") (pin "22") (pinfunction "ADBUS5_22") (pintype "bidirectional"))
    )
    (net (code "64") (name "unconnected-(IC1-ADBUS6-Pad23)") (class "Default")
      (node (ref "IC1") (pin "23") (pinfunction "ADBUS6_23") (pintype "bidirectional"))
    )
    (net (code "65") (name "unconnected-(IC1-BDBUS2-Pad28)") (class "Default")
      (node (ref "IC1") (pin "28") (pinfunction "BDBUS2_28") (pintype "bidirectional"))
    )
    (net (code "66") (name "unconnected-(IC1-BDBUS3-Pad29)") (class "Default")
      (node (ref "IC1") (pin "29") (pinfunction "BDBUS3_29") (pintype "bidirectional"))
    )
    (net (code "67") (name "unconnected-(IC1-BDBUS4-Pad30)") (class "Default")
      (node (ref "IC1") (pin "30") (pinfunction "BDBUS4_30") (pintype "bidirectional"))
    )
    (net (code "68") (name "unconnected-(IC1-BDBUS5-Pad32)") (class "Default")
      (node (ref "IC1") (pin "32") (pinfunction "BDBUS5_32") (pintype "bidirectional"))
    )
    (net (code "69") (name "unconnected-(IC1-BDBUS6-Pad33)") (class "Default")
      (node (ref "IC1") (pin "33") (pinfunction "BDBUS6_33") (pintype "bidirectional"))
    )
    (net (code "70") (name "unconnected-(IC1-CDBUS2-Pad40)") (class "Default")
      (node (ref "IC1") (pin "40") (pinfunction "CDBUS2_40") (pintype "bidirectional"))
    )
    (net (code "71") (name "unconnected-(IC1-CDBUS3-Pad41)") (class "Default")
      (node (ref "IC1") (pin "41") (pinfunction "CDBUS3_41") (pintype "bidirectional"))
    )
    (net (code "72") (name "unconnected-(IC1-CDBUS4-Pad43)") (class "Default")
      (node (ref "IC1") (pin "43") (pinfunction "CDBUS4_43") (pintype "bidirectional"))
    )
    (net (code "73") (name "unconnected-(IC1-CDBUS5-Pad44)") (class "Default")
      (node (ref "IC1") (pin "44") (pinfunction "CDBUS5_44") (pintype "bidirectional"))
    )
    (net (code "74") (name "unconnected-(IC1-CDBUS6-Pad45)") (class "Default")
      (node (ref "IC1") (pin "45") (pinfunction "CDBUS6_45") (pintype "bidirectional"))
    )
    (net (code "75") (name "unconnected-(IC1-DDBUS2-Pad53)") (class "Default")
      (node (ref "IC1") (pin "53") (pinfunction "DDBUS2_53") (pintype "bidirectional"))
    )
    (net (code "76") (name "unconnected-(IC1-DDBUS3-Pad54)") (class "Default")
      (node (ref "IC1") (pin "54") (pinfunction "DDBUS3_54") (pintype "bidirectional"))
    )
    (net (code "77") (name "unconnected-(IC1-DDBUS4-Pad55)") (class "Default")
      (node (ref "IC1") (pin "55") (pinfunction "DDBUS4_55") (pintype "bidirectional"))
    )
    (net (code "78") (name "unconnected-(IC1-DDBUS5-Pad57)") (class "Default")
      (node (ref "IC1") (pin "57") (pinfunction "DDBUS5_57") (pintype "bidirectional"))
    )
    (net (code "79") (name "unconnected-(IC1-DDBUS6-Pad58)") (class "Default")
      (node (ref "IC1") (pin "58") (pinfunction "DDBUS6_58") (pintype "bidirectional"))
    )
    (net (code "80") (name "unconnected-(IC1-SUSPEND#-Pad36)") (class "Default")
      (node (ref "IC1") (pin "36") (pinfunction "SUSPEND#_36") (pintype "bidirectional"))
    )
    (net (code "81") (name "unconnected-(IC3-EP-Pad9)") (class "Default")
      (node (ref "IC3") (pin "9") (pinfunction "EP_9") (pintype "bidirectional"))
    )
    (net (code "82") (name "unconnected-(IC4-EP-Pad9)") (class "Default")
      (node (ref "IC4") (pin "9") (pinfunction "EP_9") (pintype "bidirectional"))
    )
    (net (code "83") (name "unconnected-(IC5-EP-Pad9)") (class "Default")
      (node (ref "IC5") (pin "9") (pinfunction "EP_9") (pintype "bidirectional"))
    )
    (net (code "84") (name "unconnected-(IC6-EP-Pad9)") (class "Default")
      (node (ref "IC6") (pin "9") (pinfunction "EP_9") (pintype "bidirectional"))
    )
    (net (code "85") (name "unconnected-(IC7-QH'-Pad9)") (class "Default")
      (node (ref "IC7") (pin "9") (pinfunction "QH'_9") (pintype "bidirectional"))
    )
    (net (code "86") (name "unconnected-(USB1-CC1-PadA5)") (class "Default")
      (node (ref "USB1") (pin "A5") (pinfunction "CC1_A5") (pintype "bidirectional"))
    )
    (net (code "87") (name "unconnected-(USB1-CC2-PadB5)") (class "Default")
      (node (ref "USB1") (pin "B5") (pinfunction "CC2_B5") (pintype "bidirectional"))
    )
  )
)
